# Power.net
KiCad netlist of a schematic drawn in Altium Designer
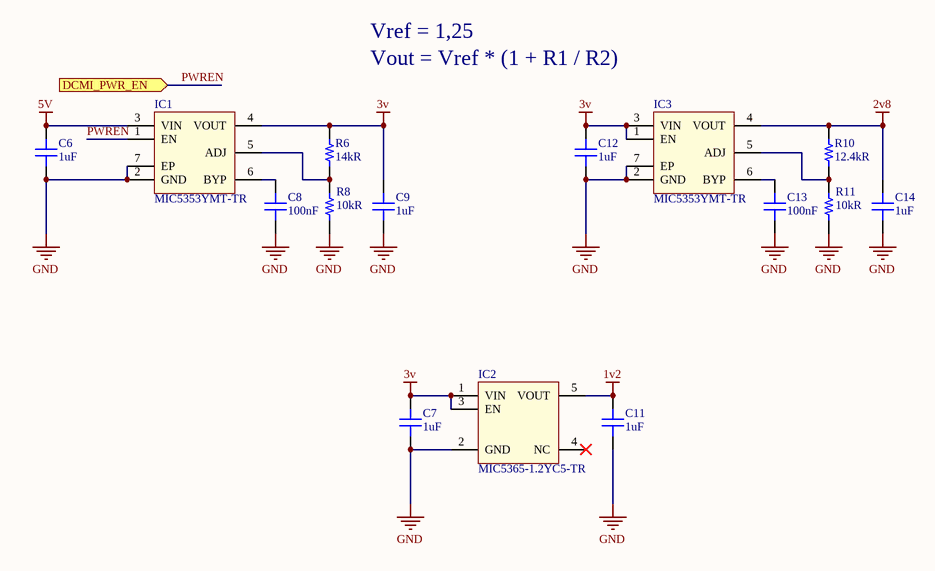
[diagram p0: Power.SchDoc]

(export (version "E")
  (design (tool "Eeschema 10.0.6"))
  (components
    (comp (ref "C6")
      (value "1uF")
      (footprint "CAP 0603/1608")
      (description "Ceramic, SMT Capacitor")
      (fields
        (field (name "MANUFACTURER") "Samsung")
        (field (name "MANUFACTURER PART NUMBER") "CL10A105KP8NNNC")
      )
      (libsource (lib "yildizIoT Library") (part "Capacitor - Ceramic"))
    )
    (comp (ref "C7")
      (value "1uF")
      (footprint "CAP 0603/1608")
      (description "Ceramic, SMT Capacitor")
      (fields
        (field (name "MANUFACTURER") "Samsung")
        (field (name "MANUFACTURER PART NUMBER") "CL10A105KP8NNNC")
      )
      (libsource (lib "yildizIoT Library") (part "Capacitor - Ceramic"))
    )
    (comp (ref "C8")
      (value "100nF")
      (footprint "CAP 0603/1608")
      (description "Ceramic, SMT Capacitor")
      (fields
        (field (name "MANUFACTURER") "Samsung")
        (field (name "MANUFACTURER PART NUMBER") "CL10B104JB8NNNC")
      )
      (libsource (lib "yildizIoT Library") (part "Capacitor - Ceramic"))
    )
    (comp (ref "C9")
      (value "1uF")
      (footprint "CAP 0603/1608")
      (description "Ceramic, SMT Capacitor")
      (fields
        (field (name "MANUFACTURER") "Samsung")
        (field (name "MANUFACTURER PART NUMBER") "CL10A105KP8NNNC")
      )
      (libsource (lib "yildizIoT Library") (part "Capacitor - Ceramic"))
    )
    (comp (ref "C11")
      (value "1uF")
      (footprint "CAP 0603/1608")
      (description "Ceramic, SMT Capacitor")
      (fields
        (field (name "MANUFACTURER") "Samsung")
        (field (name "MANUFACTURER PART NUMBER") "CL10A105KP8NNNC")
      )
      (libsource (lib "yildizIoT Library") (part "Capacitor - Ceramic"))
    )
    (comp (ref "C12")
      (value "1uF")
      (footprint "CAP 0603/1608")
      (description "Ceramic, SMT Capacitor")
      (fields
        (field (name "MANUFACTURER") "Samsung")
        (field (name "MANUFACTURER PART NUMBER") "CL10A105KP8NNNC")
      )
      (libsource (lib "yildizIoT Library") (part "Capacitor - Ceramic"))
    )
    (comp (ref "C13")
      (value "100nF")
      (footprint "CAP 0603/1608")
      (description "Ceramic, SMT Capacitor")
      (fields
        (field (name "MANUFACTURER") "Samsung")
        (field (name "MANUFACTURER PART NUMBER") "CL10B104JB8NNNC")
      )
      (libsource (lib "yildizIoT Library") (part "Capacitor - Ceramic"))
    )
    (comp (ref "C14")
      (value "1uF")
      (footprint "CAP 0603/1608")
      (description "Ceramic, SMT Capacitor")
      (fields
        (field (name "MANUFACTURER") "Samsung")
        (field (name "MANUFACTURER PART NUMBER") "CL10A105KP8NNNC")
      )
      (libsource (lib "yildizIoT Library") (part "Capacitor - Ceramic"))
    )
    (comp (ref "IC1")
      (value "MIC5353YMT-TR")
      (footprint "MICREL MLF-6 1.6x1.6MM")
      (description "Integrated Circuit")
      (fields (field (name "MANUFACTURER") "Microchip"))
      (libsource (lib "yildizIoT Library") (part "MICROCHIP MIC5353"))
    )
    (comp (ref "IC2")
      (value "MIC5365-1.2YC5-TR")
      (footprint "MICROCHIP SC70-5 LT")
      (description "Linear Voltage Regulator IC Positive Fixed 1 Output 1.2V 150mA SC-70-5")
      (fields (field (name "MANUFACTURER") "Microchip"))
      (libsource (lib "yildizIoT Library") (part "MICROCHIP MIC5365/6-xxYC"))
    )
    (comp (ref "IC3")
      (value "MIC5353YMT-TR")
      (footprint "MICREL MLF-6 1.6x1.6MM")
      (description "Integrated Circuit")
      (fields (field (name "MANUFACTURER") "Microchip"))
      (libsource (lib "yildizIoT Library") (part "MICROCHIP MIC5353"))
    )
    (comp (ref "R6")
      (value "14kR")
      (footprint "RES 0603/1608")
      (description "Ceramic, SMT Capacitor")
      (fields
        (field (name "MANUFACTURER") "Yageo")
        (field (name "MANUFACTURER PART NUMBER") "RC0603FR-0714KL")
      )
      (libsource (lib "yildizIoT Library") (part "Resistor_Chip"))
    )
    (comp (ref "R8")
      (value "10kR")
      (footprint "RES 0603/1608")
      (description "Ceramic, SMT Capacitor")
      (fields
        (field (name "MANUFACTURER") "Stackpole Electronics")
        (field (name "MANUFACTURER PART NUMBER") "RNCP0603FTD10K0")
      )
      (libsource (lib "yildizIoT Library") (part "Resistor_Chip"))
    )
    (comp (ref "R10")
      (value "12.4kR")
      (footprint "RES 0603/1608")
      (description "Ceramic, SMT Capacitor")
      (fields
        (field (name "MANUFACTURER") "Yageo")
        (field (name "MANUFACTURER PART NUMBER") "RC0603FR-0712K4L")
      )
      (libsource (lib "yildizIoT Library") (part "Resistor_Chip"))
    )
    (comp (ref "R11")
      (value "10kR")
      (footprint "RES 0603/1608")
      (description "Ceramic, SMT Capacitor")
      (fields
        (field (name "MANUFACTURER") "Stackpole Electronics")
        (field (name "MANUFACTURER PART NUMBER") "RNCP0603FTD10K0")
      )
      (libsource (lib "yildizIoT Library") (part "Resistor_Chip"))
    )
  )
  (nets
    (net (code "1") (name "/PWREN") (class "Default")
      (node (ref "IC1") (pin "1") (pinfunction "EN_1") (pintype "passive"))
    )
    (net (code "2") (name "1v2") (class "Default")
      (node (ref "C11") (pin "2") (pinfunction "2_2") (pintype "passive"))
      (node (ref "IC2") (pin "5") (pinfunction "VOUT_5") (pintype "passive"))
    )
    (net (code "3") (name "2v8") (class "Default")
      (node (ref "C14") (pin "2") (pinfunction "2_2") (pintype "passive"))
      (node (ref "IC3") (pin "4") (pinfunction "VOUT_4") (pintype "passive"))
      (node (ref "R10") (pin "2") (pinfunction "2_2") (pintype "passive"))
    )
    (net (code "4") (name "3v") (class "Default")
      (node (ref "C12") (pin "2") (pinfunction "2_2") (pintype "passive"))
      (node (ref "C7") (pin "2") (pinfunction "2_2") (pintype "passive"))
      (node (ref "C9") (pin "2") (pinfunction "2_2") (pintype "passive"))
      (node (ref "IC1") (pin "4") (pinfunction "VOUT_4") (pintype "passive"))
      (node (ref "IC2") (pin "1") (pinfunction "VIN_1") (pintype "passive"))
      (node (ref "IC2") (pin "3") (pinfunction "EN_3") (pintype "passive"))
      (node (ref "IC3") (pin "1") (pinfunction "EN_1") (pintype "passive"))
      (node (ref "IC3") (pin "3") (pinfunction "VIN_3") (pintype "passive"))
      (node (ref "R6") (pin "2") (pinfunction "2_2") (pintype "passive"))
    )
    (net (code "5") (name "5V") (class "Default")
      (node (ref "C6") (pin "2") (pinfunction "2_2") (pintype "passive"))
      (node (ref "IC1") (pin "3") (pinfunction "VIN_3") (pintype "passive"))
    )
    (net (code "6") (name "GND") (class "Default")
      (node (ref "C11") (pin "1") (pinfunction "1_1") (pintype "passive"))
      (node (ref "C12") (pin "1") (pinfunction "1_1") (pintype "passive"))
      (node (ref "C13") (pin "1") (pinfunction "1_1") (pintype "passive"))
      (node (ref "C14") (pin "1") (pinfunction "1_1") (pintype "passive"))
      (node (ref "C6") (pin "1") (pinfunction "1_1") (pintype "passive"))
      (node (ref "C7") (pin "1") (pinfunction "1_1") (pintype "passive"))
      (node (ref "C8") (pin "1") (pinfunction "1_1") (pintype "passive"))
      (node (ref "C9") (pin "1") (pinfunction "1_1") (pintype "passive"))
      (node (ref "IC1") (pin "2") (pinfunction "GND_2") (pintype "passive"))
      (node (ref "IC1") (pin "7") (pinfunction "EP_7") (pintype "power_in"))
      (node (ref "IC2") (pin "2") (pinfunction "GND_2") (pintype "passive"))
      (node (ref "IC3") (pin "2") (pinfunction "GND_2") (pintype "passive"))
      (node (ref "IC3") (pin "7") (pinfunction "EP_7") (pintype "power_in"))
      (node (ref "R11") (pin "2") (pinfunction "2_2") (pintype "passive"))
      (node (ref "R8") (pin "2") (pinfunction "2_2") (pintype "passive"))
    )
    (net (code "7") (name "Net-(IC1-ADJ)") (class "Default")
      (node (ref "IC1") (pin "5") (pinfunction "ADJ_5") (pintype "passive"))
      (node (ref "R6") (pin "1") (pinfunction "1_1") (pintype "passive"))
      (node (ref "R8") (pin "1") (pinfunction "1_1") (pintype "passive"))
    )
    (net (code "8") (name "Net-(IC1-BYP)") (class "Default")
      (node (ref "C8") (pin "2") (pinfunction "2_2") (pintype "passive"))
      (node (ref "IC1") (pin "6") (pinfunction "BYP_6") (pintype "passive"))
    )
    (net (code "9") (name "Net-(IC3-ADJ)") (class "Default")
      (node (ref "IC3") (pin "5") (pinfunction "ADJ_5") (pintype "passive"))
      (node (ref "R10") (pin "1") (pinfunction "1_1") (pintype "passive"))
      (node (ref "R11") (pin "1") (pinfunction "1_1") (pintype "passive"))
    )
    (net (code "10") (name "Net-(IC3-BYP)") (class "Default")
      (node (ref "C13") (pin "2") (pinfunction "2_2") (pintype "passive"))
      (node (ref "IC3") (pin "6") (pinfunction "BYP_6") (pintype "passive"))
    )
    (net (code "11") (name "unconnected-(IC2-NC-Pad4)") (class "Default")
      (node (ref "IC2") (pin "4") (pinfunction "NC_4") (pintype "passive+no_connect"))
    )
  )
)
